# Fan_MOSFET_Channel.net
KiCad netlist of a schematic drawn in Altium Designer
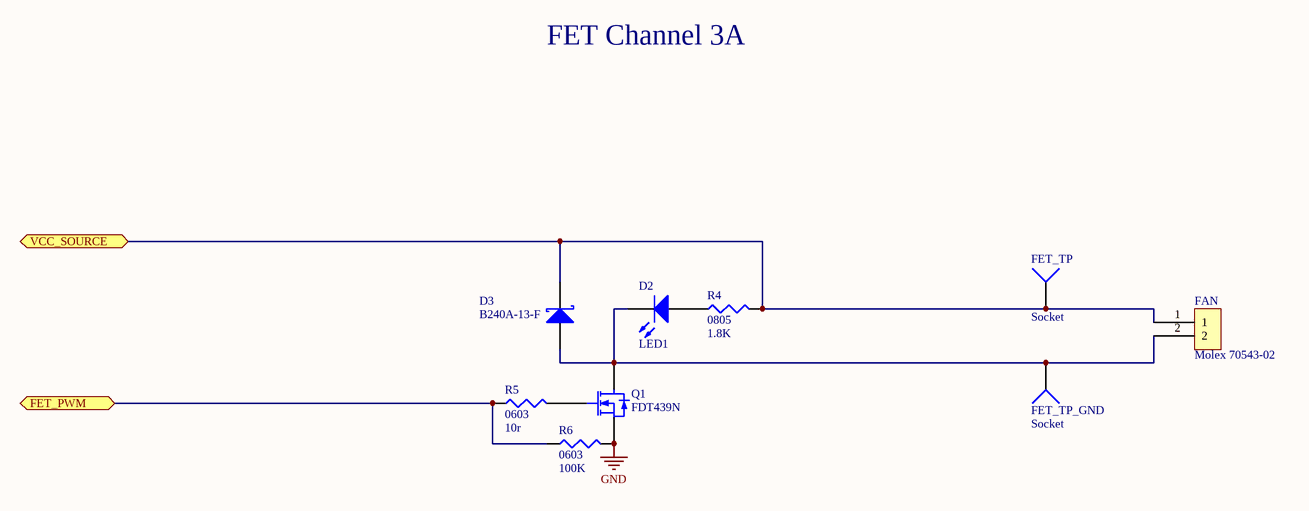
[diagram p0: Fan MOSFET Channel.SchDoc]

(export (version "E")
  (design (tool "Eeschema 10.0.6"))
  (components
    (comp (ref "D2")
      (value "LED1")
      (footprint "SM 0805 polarized")
      (description "Typical RED GaAs LED")
      (fields (field (name "PUBLISHER") "Altium Limited"))
      (libsource (lib "Miscellaneous Devices") (part "LED1"))
    )
    (comp (ref "D3")
      (value "B240A-13-F")
      (footprint "SMB")
      (description "Schottky Diode")
      (fields (field (name "PUBLISHER") "Altium Limited"))
      (libsource (lib "Miscellaneous Devices") (part "D Schottky"))
    )
    (comp (ref "FAN")
      (value "Molex 70543-02")
      (footprint "70543-02")
      (libsource (lib "ZMBo Schematic Library") (part "Molex 70543-02"))
    )
    (comp (ref "FET_TP")
      (value "Socket")
      (footprint "PIN1")
      (fields (field (name "PUBLISHER") "Altium Limited"))
      (libsource (lib "Miscellaneous Connectors") (part "Socket"))
    )
    (comp (ref "FET_TP_GND")
      (value "Socket")
      (footprint "PIN1")
      (fields (field (name "PUBLISHER") "Altium Limited"))
      (libsource (lib "Miscellaneous Connectors") (part "Socket"))
    )
    (comp (ref "Q1")
      (value "FDT439N")
      (footprint "Fairchild FDT439N")
      (description "N-Channel MOSFET")
      (fields (field (name "PUBLISHER") "Altium Limited"))
      (libsource (lib "ZMBo Schematic Library") (part "Fairchild FDT439N"))
    )
    (comp (ref "R4")
      (value "0805")
      (footprint "SM 0805 - gap trimmed")
      (description "Resistor")
      (fields (field (name "ALTIUM_VALUE") "1.8K") (field (name "PUBLISHER") "Altium Limited"))
      (libsource (lib "Miscellaneous Devices") (part "Res3"))
    )
    (comp (ref "R5")
      (value "0603")
      (footprint "J1-0603")
      (description "Resistor")
      (fields (field (name "ALTIUM_VALUE") "10r") (field (name "PUBLISHER") "Altium Limited"))
      (libsource (lib "Miscellaneous Devices") (part "Res3"))
    )
    (comp (ref "R6")
      (value "0603")
      (footprint "J1-0603")
      (description "Resistor")
      (fields (field (name "ALTIUM_VALUE") "100K") (field (name "PUBLISHER") "Altium Limited"))
      (libsource (lib "Miscellaneous Devices") (part "Res3"))
    )
  )
  (nets
    (net (code "1") (name "/FET_PWM") (class "Default")
      (node (ref "R5") (pin "1") (pinfunction "1_1") (pintype "passive"))
      (node (ref "R6") (pin "1") (pinfunction "1_1") (pintype "passive"))
    )
    (net (code "2") (name "/VCC_SOURCE") (class "Default")
      (node (ref "D3") (pin "2") (pinfunction "K_2") (pintype "passive"))
      (node (ref "FAN") (pin "1") (pinfunction "1_1") (pintype "passive"))
      (node (ref "FET_TP") (pin "1") (pinfunction "1_1") (pintype "passive"))
      (node (ref "R4") (pin "2") (pinfunction "2_2") (pintype "passive"))
    )
    (net (code "3") (name "2") (class "Default")
      (node (ref "Q1") (pin "4") (pinfunction "D_4") (pintype "passive"))
    )
    (net (code "4") (name "GND") (class "Default")
      (node (ref "Q1") (pin "3") (pinfunction "S_3") (pintype "passive"))
      (node (ref "R6") (pin "2") (pinfunction "2_2") (pintype "passive"))
    )
    (net (code "5") (name "Net-(D2-A)") (class "Default")
      (node (ref "D2") (pin "1") (pinfunction "A_1") (pintype "passive"))
      (node (ref "R4") (pin "1") (pinfunction "1_1") (pintype "passive"))
    )
    (net (code "6") (name "Net-(D2-K)") (class "Default")
      (node (ref "D2") (pin "2") (pinfunction "K_2") (pintype "passive"))
      (node (ref "D3") (pin "1") (pinfunction "A_1") (pintype "passive"))
      (node (ref "FAN") (pin "2") (pinfunction "2_2") (pintype "passive"))
      (node (ref "FET_TP_GND") (pin "1") (pinfunction "1_1") (pintype "passive"))
      (node (ref "Q1") (pin "2") (pinfunction "D_2") (pintype "passive"))
    )
    (net (code "7") (name "Net-(Q1-G)") (class "Default")
      (node (ref "Q1") (pin "1") (pinfunction "G_1") (pintype "passive"))
      (node (ref "R5") (pin "2") (pinfunction "2_2") (pintype "passive"))
    )
  )
)
